# 03_GSM_GPRS_GPS.net
KiCad netlist of a schematic drawn in Altium Designer
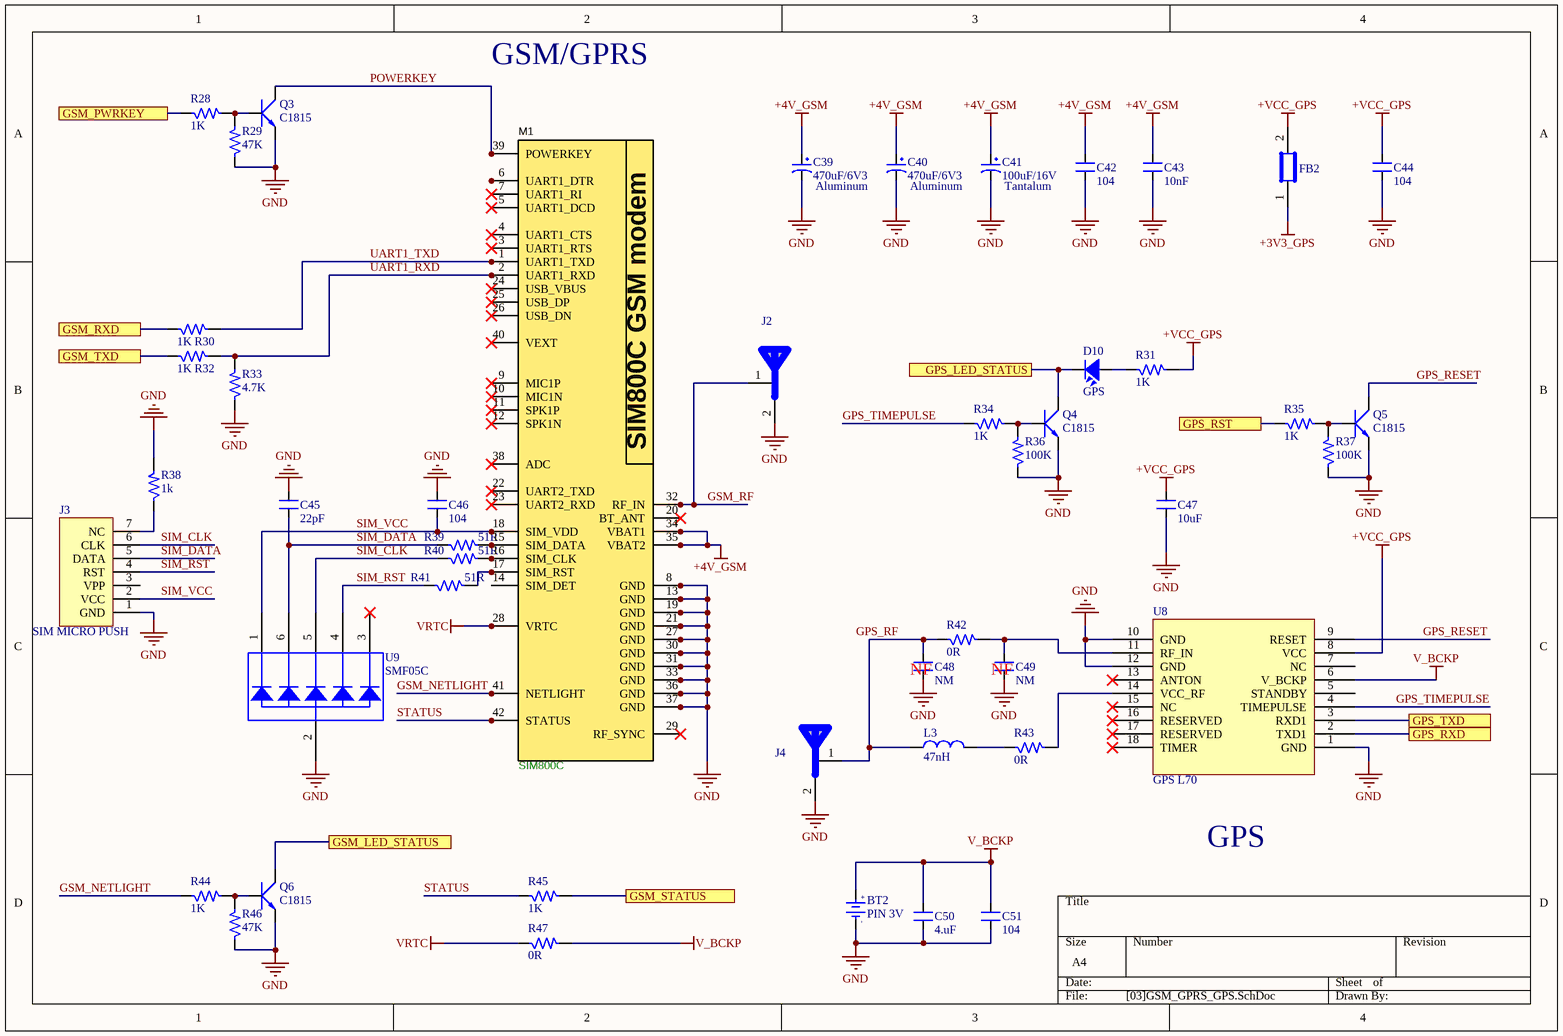
[diagram p0: [03]GSM_GPRS_GPS.SchDoc]

(export (version "E")
  (design (tool "Eeschema 10.0.6"))
  (components
    (comp (ref "BT2")
      (value "PIN 3V")
      (footprint "My Library:CR1220 SMD")
      (description "Battery 3VDC")
      (libsource (lib "GPS_Traking_V1_1") (part "PIN 3V"))
    )
    (comp (ref "C39")
      (value "470uF/6V3")
      (footprint "C_Alu_6.3x7.7")
      (description "Cap Aluminum")
      (libsource (lib "GPS_Traking_V1_1") (part "C-Alu-Tantalum"))
    )
    (comp (ref "C40")
      (value "470uF/6V3")
      (footprint "C_Alu_6.3x7.7")
      (description "Cap Aluminum")
      (libsource (lib "GPS_Traking_V1_1") (part "C-Alu-Tantalum"))
    )
    (comp (ref "C41")
      (value "100uF/16V")
      (footprint "C_7343_40")
      (description "Cap Tantalum 7343")
      (libsource (lib "GPS_Traking_V1_1") (part "C-Alu-Tantalum"))
    )
    (comp (ref "C42")
      (value "104")
      (footprint "CAP_0805")
      (description "Cap SMD")
      (libsource (lib "GPS_Traking_V1_1") (part "CM"))
    )
    (comp (ref "C43")
      (value "10nF")
      (footprint "CAP_0805")
      (description "Cap SMD")
      (libsource (lib "GPS_Traking_V1_1") (part "CM"))
    )
    (comp (ref "C44")
      (value "104")
      (footprint "CAP_0805")
      (description "Cap SMD")
      (libsource (lib "GPS_Traking_V1_1") (part "CM"))
    )
    (comp (ref "C45")
      (value "22pF")
      (footprint "C0603 SMT")
      (description "Cap SMD")
      (libsource (lib "GPS_Traking_V1_1") (part "CM"))
    )
    (comp (ref "C46")
      (value "104")
      (footprint "C0603 SMT")
      (description "Cap SMD")
      (libsource (lib "GPS_Traking_V1_1") (part "CM"))
    )
    (comp (ref "C47")
      (value "10uF")
      (footprint "CAP_0805")
      (description "Cap SMD")
      (libsource (lib "GPS_Traking_V1_1") (part "CM"))
    )
    (comp (ref "C48")
      (value "NM")
      (footprint "C0603 SMT")
      (description "Cap SMD")
      (libsource (lib "GPS_Traking_V1_1") (part "CM"))
    )
    (comp (ref "C49")
      (value "NM")
      (footprint "C0603 SMT")
      (description "Cap SMD")
      (libsource (lib "GPS_Traking_V1_1") (part "CM"))
    )
    (comp (ref "C50")
      (value "4.uF")
      (footprint "SM-1210")
      (description "Cap SMD")
      (libsource (lib "GPS_Traking_V1_1") (part "CM"))
    )
    (comp (ref "C51")
      (value "104")
      (footprint "CAP_0805")
      (description "Cap SMD")
      (libsource (lib "GPS_Traking_V1_1") (part "CM"))
    )
    (comp (ref "D10")
      (value "GPS")
      (footprint "LED-0805-Red")
      (description "LED Single colour Green and Red")
      (libsource (lib "GPS_Traking_V1_1") (part "LED"))
    )
    (comp (ref "FB2")
      (value "BLM21PG600SN1D")
      (footprint "R0805")
      (description "Ferrite Bead")
      (libsource (lib "GPS_Traking_V1_1") (part "Ferrite Bead"))
    )
    (comp (ref "J2")
      (value "GPS_ANTENNA")
      (footprint "Antenna-MCX5.08-H5")
      (libsource (lib "GPS_Traking_V1_1") (part "ANTEN"))
    )
    (comp (ref "J3")
      (value "SIM MICRO PUSH")
      (footprint "My Library:MICROSIM_PUSH")
      (libsource (lib "My Library") (part "SIM MICRO PUSH"))
    )
    (comp (ref "J4")
      (value "GPS_ANTENNA")
      (footprint "Antenna-MCX5.08-H5")
      (libsource (lib "GPS_Traking_V1_1") (part "ANTEN"))
    )
    (comp (ref "L3")
      (value "47nH")
      (footprint "RES-SMD-0805")
      (description "Inductor")
      (libsource (lib "GPS_Traking_V1_1") (part "L1"))
    )
    (comp (ref "M1")
      (value "SIM800C")
      (footprint "SIM800C")
      (libsource (lib "GPS_Traking_V1_1") (part "SIM800C"))
    )
    (comp (ref "Q3")
      (value "C1815")
      (footprint "SOT23B")
      (description "NPN 600mW, ECB")
      (libsource (lib "GPS_Traking_V1_1") (part "C1815"))
    )
    (comp (ref "Q4")
      (value "C1815")
      (footprint "SOT23B")
      (description "NPN 600mW, ECB")
      (libsource (lib "GPS_Traking_V1_1") (part "C1815"))
    )
    (comp (ref "Q5")
      (value "C1815")
      (footprint "SOT23B")
      (description "NPN 600mW, ECB")
      (libsource (lib "GPS_Traking_V1_1") (part "C1815"))
    )
    (comp (ref "Q6")
      (value "C1815")
      (footprint "SOT23B")
      (description "NPN 600mW, ECB")
      (libsource (lib "GPS_Traking_V1_1") (part "C1815"))
    )
    (comp (ref "R28")
      (value "1K")
      (footprint "R0603 -SMT")
      (description "Resistor SMD")
      (libsource (lib "GPS_Traking_V1_1") (part "RM"))
    )
    (comp (ref "R29")
      (value "47K")
      (footprint "R0603 -SMT")
      (description "Resistor SMD")
      (libsource (lib "GPS_Traking_V1_1") (part "RM"))
    )
    (comp (ref "R30")
      (value "1K")
      (footprint "R0603 -SMT")
      (description "Resistor SMD")
      (libsource (lib "GPS_Traking_V1_1") (part "RM"))
    )
    (comp (ref "R31")
      (value "1K")
      (footprint "RES-SMD-0805")
      (description "Resistor SMD")
      (libsource (lib "GPS_Traking_V1_1") (part "RM"))
    )
    (comp (ref "R32")
      (value "1K")
      (footprint "R0603 -SMT")
      (description "Resistor SMD")
      (libsource (lib "GPS_Traking_V1_1") (part "RM"))
    )
    (comp (ref "R33")
      (value "4.7K")
      (footprint "R0603 -SMT")
      (description "Resistor SMD")
      (libsource (lib "GPS_Traking_V1_1") (part "RM"))
    )
    (comp (ref "R34")
      (value "1K")
      (footprint "RES-SMD-0805")
      (description "Resistor SMD")
      (libsource (lib "GPS_Traking_V1_1") (part "RM"))
    )
    (comp (ref "R35")
      (value "1K")
      (footprint "RES-SMD-0805")
      (description "Resistor SMD")
      (libsource (lib "GPS_Traking_V1_1") (part "RM"))
    )
    (comp (ref "R36")
      (value "100K")
      (footprint "RES-SMD-0805")
      (description "Resistor SMD")
      (libsource (lib "GPS_Traking_V1_1") (part "RM"))
    )
    (comp (ref "R37")
      (value "100K")
      (footprint "RES-SMD-0805")
      (description "Resistor SMD")
      (libsource (lib "GPS_Traking_V1_1") (part "RM"))
    )
    (comp (ref "R38")
      (value "1k")
      (footprint "RES-SMD-0805")
      (description "Resistor SMD")
      (libsource (lib "GPS_Traking_V1_1") (part "RM"))
    )
    (comp (ref "R39")
      (value "51R")
      (footprint "R0603 -SMT")
      (description "Resistor SMD")
      (libsource (lib "GPS_Traking_V1_1") (part "RM"))
    )
    (comp (ref "R40")
      (value "51R")
      (footprint "R0603 -SMT")
      (description "Resistor SMD")
      (libsource (lib "GPS_Traking_V1_1") (part "RM"))
    )
    (comp (ref "R41")
      (value "51R")
      (footprint "R0603 -SMT")
      (description "Resistor SMD")
      (libsource (lib "GPS_Traking_V1_1") (part "RM"))
    )
    (comp (ref "R42")
      (value "0R")
      (footprint "R0603 -SMT")
      (description "Resistor SMD")
      (libsource (lib "GPS_Traking_V1_1") (part "RM"))
    )
    (comp (ref "R43")
      (value "0R")
      (footprint "R0603 -SMT")
      (description "Resistor SMD")
      (libsource (lib "GPS_Traking_V1_1") (part "RM"))
    )
    (comp (ref "R44")
      (value "1K")
      (footprint "R0603 -SMT")
      (description "Resistor SMD")
      (libsource (lib "GPS_Traking_V1_1") (part "RM"))
    )
    (comp (ref "R45")
      (value "1K")
      (footprint "R0603 -SMT")
      (description "Resistor SMD")
      (libsource (lib "GPS_Traking_V1_1") (part "RM"))
    )
    (comp (ref "R46")
      (value "47K")
      (footprint "R0603 -SMT")
      (description "Resistor SMD")
      (libsource (lib "GPS_Traking_V1_1") (part "RM"))
    )
    (comp (ref "R47")
      (value "0R")
      (footprint "RES-SMD-0805")
      (description "Resistor SMD")
      (libsource (lib "GPS_Traking_V1_1") (part "RM"))
    )
    (comp (ref "U8")
      (value "GPS L70")
      (footprint "GPS L70")
      (libsource (lib "GPS_Traking_V1_1") (part "GPS L70"))
    )
    (comp (ref "U9")
      (value "SMF05C")
      (footprint "SOT_363_6")
      (description "ESD Protection")
      (libsource (lib "GPS_Traking_V1_1") (part "SMF05C"))
    )
  )
  (nets
    (net (code "1") (name "+3V3_GPS") (class "Default")
      (node (ref "FB2") (pin "1") (pinfunction "1_1") (pintype "passive"))
    )
    (net (code "2") (name "+4V_GSM") (class "Default")
      (node (ref "C39") (pin "1") (pinfunction "1_1") (pintype "passive"))
      (node (ref "C40") (pin "1") (pinfunction "1_1") (pintype "passive"))
      (node (ref "C41") (pin "1") (pinfunction "1_1") (pintype "passive"))
      (node (ref "C42") (pin "1") (pinfunction "1_1") (pintype "passive"))
      (node (ref "C43") (pin "1") (pinfunction "1_1") (pintype "passive"))
      (node (ref "M1") (pin "34") (pinfunction "VBAT1_34") (pintype "passive"))
      (node (ref "M1") (pin "35") (pinfunction "VBAT2_35") (pintype "passive"))
    )
    (net (code "3") (name "+VCC_GPS") (class "Default")
      (node (ref "C44") (pin "2") (pinfunction "2_2") (pintype "passive"))
      (node (ref "C47") (pin "2") (pinfunction "2_2") (pintype "passive"))
      (node (ref "FB2") (pin "2") (pinfunction "2_2") (pintype "passive"))
      (node (ref "R31") (pin "2") (pinfunction "2_2") (pintype "passive"))
      (node (ref "U8") (pin "8") (pinfunction "VCC_8") (pintype "passive"))
    )
    (net (code "4") (name "/GPS_LED_STATUS") (class "Default")
      (node (ref "D10") (pin "2") (pinfunction "2_2") (pintype "passive"))
      (node (ref "Q4") (pin "2") (pinfunction "C_2") (pintype "passive"))
    )
    (net (code "5") (name "/GPS_RESET") (class "Default")
      (node (ref "Q5") (pin "2") (pinfunction "C_2") (pintype "passive"))
      (node (ref "U8") (pin "9") (pinfunction "RESET_9") (pintype "passive"))
    )
    (net (code "7") (name "/GPS_RST") (class "Default")
      (node (ref "R35") (pin "1") (pinfunction "1_1") (pintype "passive"))
    )
    (net (code "8") (name "/GPS_RXD") (class "Default")
      (node (ref "U8") (pin "2") (pinfunction "TXD1_2") (pintype "passive"))
    )
    (net (code "9") (name "/GPS_TIMEPULSE") (class "Default")
      (node (ref "R34") (pin "1") (pinfunction "1_1") (pintype "passive"))
      (node (ref "U8") (pin "4") (pinfunction "TIMEPULSE_4") (pintype "passive"))
    )
    (net (code "10") (name "/GPS_TXD") (class "Default")
      (node (ref "U8") (pin "3") (pinfunction "RXD1_3") (pintype "passive"))
    )
    (net (code "11") (name "/GSM_LED_STATUS") (class "Default")
      (node (ref "Q6") (pin "2") (pinfunction "C_2") (pintype "passive"))
    )
    (net (code "12") (name "/GSM_NETLIGHT") (class "Default")
      (node (ref "M1") (pin "41") (pinfunction "NETLIGHT_41") (pintype "passive"))
      (node (ref "R44") (pin "1") (pinfunction "1_1") (pintype "passive"))
    )
    (net (code "13") (name "/GSM_PWRKEY") (class "Default")
      (node (ref "R28") (pin "1") (pinfunction "1_1") (pintype "passive"))
    )
    (net (code "14") (name "/GSM_RF") (class "Default")
      (node (ref "J2") (pin "1") (pinfunction "GND_1") (pintype "passive"))
      (node (ref "M1") (pin "32") (pinfunction "RF_IN_32") (pintype "passive"))
    )
    (net (code "15") (name "/GSM_RXD") (class "Default")
      (node (ref "R30") (pin "1") (pinfunction "1_1") (pintype "passive"))
    )
    (net (code "16") (name "/GSM_STATUS") (class "Default")
      (node (ref "R45") (pin "2") (pinfunction "2_2") (pintype "passive"))
    )
    (net (code "17") (name "/GSM_TXD") (class "Default")
      (node (ref "R32") (pin "1") (pinfunction "1_1") (pintype "passive"))
    )
    (net (code "18") (name "/POWERKEY") (class "Default")
      (node (ref "M1") (pin "39") (pinfunction "POWERKEY_39") (pintype "passive"))
      (node (ref "Q3") (pin "2") (pinfunction "C_2") (pintype "passive"))
    )
    (net (code "19") (name "/SIM_CLK") (class "Default")
      (node (ref "J3") (pin "6") (pinfunction "CLK_6") (pintype "passive"))
      (node (ref "R40") (pin "1") (pinfunction "1_1") (pintype "passive"))
      (node (ref "U9") (pin "5") (pinfunction "K4_5") (pintype "power_in"))
    )
    (net (code "20") (name "/SIM_DATA") (class "Default")
      (node (ref "C45") (pin "1") (pinfunction "1_1") (pintype "passive"))
      (node (ref "J3") (pin "5") (pinfunction "DATA_5") (pintype "passive"))
      (node (ref "R39") (pin "1") (pinfunction "1_1") (pintype "passive"))
      (node (ref "U9") (pin "6") (pinfunction "K5_6") (pintype "passive"))
    )
    (net (code "21") (name "/SIM_RST") (class "Default")
      (node (ref "J3") (pin "4") (pinfunction "RST_4") (pintype "passive"))
      (node (ref "R41") (pin "1") (pinfunction "1_1") (pintype "passive"))
      (node (ref "U9") (pin "4") (pinfunction "K3_4") (pintype "passive"))
    )
    (net (code "22") (name "/SIM_VCC") (class "Default")
      (node (ref "C46") (pin "1") (pinfunction "1_1") (pintype "passive"))
      (node (ref "J3") (pin "2") (pinfunction "VCC_2") (pintype "passive"))
      (node (ref "M1") (pin "18") (pinfunction "SIM_VDD_18") (pintype "passive"))
      (node (ref "U9") (pin "1") (pinfunction "K1_1") (pintype "passive"))
    )
    (net (code "23") (name "/STATUS") (class "Default")
      (node (ref "M1") (pin "42") (pinfunction "STATUS_42") (pintype "passive"))
      (node (ref "R45") (pin "1") (pinfunction "1_1") (pintype "passive"))
    )
    (net (code "24") (name "/UART1_RXD") (class "Default")
      (node (ref "M1") (pin "2") (pinfunction "UART1_RXD_2") (pintype "passive"))
      (node (ref "R32") (pin "2") (pinfunction "2_2") (pintype "passive"))
      (node (ref "R33") (pin "2") (pinfunction "2_2") (pintype "passive"))
    )
    (net (code "25") (name "/UART1_TXD") (class "Default")
      (node (ref "M1") (pin "1") (pinfunction "UART1_TXD_1") (pintype "passive"))
      (node (ref "R30") (pin "2") (pinfunction "2_2") (pintype "passive"))
    )
    (net (code "26") (name "GND") (class "Default")
      (node (ref "BT2") (pin "2") (pinfunction "GND_2") (pintype "passive"))
      (node (ref "C39") (pin "2") (pinfunction "2_2") (pintype "passive"))
      (node (ref "C40") (pin "2") (pinfunction "2_2") (pintype "passive"))
      (node (ref "C41") (pin "2") (pinfunction "2_2") (pintype "passive"))
      (node (ref "C42") (pin "2") (pinfunction "2_2") (pintype "passive"))
      (node (ref "C43") (pin "2") (pinfunction "2_2") (pintype "passive"))
      (node (ref "C44") (pin "1") (pinfunction "1_1") (pintype "passive"))
      (node (ref "C45") (pin "2") (pinfunction "2_2") (pintype "passive"))
      (node (ref "C46") (pin "2") (pinfunction "2_2") (pintype "passive"))
      (node (ref "C47") (pin "1") (pinfunction "1_1") (pintype "passive"))
      (node (ref "C48") (pin "1") (pinfunction "1_1") (pintype "passive"))
      (node (ref "C49") (pin "1") (pinfunction "1_1") (pintype "passive"))
      (node (ref "C50") (pin "1") (pinfunction "1_1") (pintype "passive"))
      (node (ref "C51") (pin "1") (pinfunction "1_1") (pintype "passive"))
      (node (ref "J2") (pin "2") (pinfunction "GND_2") (pintype "passive"))
      (node (ref "J3") (pin "1") (pinfunction "GND_1") (pintype "passive"))
      (node (ref "J4") (pin "2") (pinfunction "GND_2") (pintype "passive"))
      (node (ref "M1") (pin "13") (pinfunction "GND_13") (pintype "passive"))
      (node (ref "M1") (pin "19") (pinfunction "GND_19") (pintype "passive"))
      (node (ref "M1") (pin "21") (pinfunction "GND_21") (pintype "passive"))
      (node (ref "M1") (pin "27") (pinfunction "GND_27") (pintype "passive"))
      (node (ref "M1") (pin "30") (pinfunction "GND_30") (pintype "passive"))
      (node (ref "M1") (pin "31") (pinfunction "GND_31") (pintype "passive"))
      (node (ref "M1") (pin "33") (pinfunction "GND_33") (pintype "passive"))
      (node (ref "M1") (pin "36") (pinfunction "GND_36") (pintype "passive"))
      (node (ref "M1") (pin "37") (pinfunction "GND_37") (pintype "passive"))
      (node (ref "M1") (pin "8") (pinfunction "GND_8") (pintype "passive"))
      (node (ref "Q3") (pin "1") (pinfunction "E_1") (pintype "passive"))
      (node (ref "Q4") (pin "1") (pinfunction "E_1") (pintype "passive"))
      (node (ref "Q5") (pin "1") (pinfunction "E_1") (pintype "passive"))
      (node (ref "Q6") (pin "1") (pinfunction "E_1") (pintype "passive"))
      (node (ref "R29") (pin "1") (pinfunction "1_1") (pintype "passive"))
      (node (ref "R33") (pin "1") (pinfunction "1_1") (pintype "passive"))
      (node (ref "R36") (pin "1") (pinfunction "1_1") (pintype "passive"))
      (node (ref "R37") (pin "1") (pinfunction "1_1") (pintype "passive"))
      (node (ref "R38") (pin "2") (pinfunction "2_2") (pintype "passive"))
      (node (ref "R46") (pin "1") (pinfunction "1_1") (pintype "passive"))
      (node (ref "U8") (pin "1") (pinfunction "GND_1") (pintype "passive"))
      (node (ref "U8") (pin "10") (pinfunction "GND_10") (pintype "passive"))
      (node (ref "U8") (pin "12") (pinfunction "GND_12") (pintype "passive"))
      (node (ref "U9") (pin "2") (pinfunction "A_2") (pintype "power_in"))
    )
    (net (code "27") (name "Net-(C48-Pad2)") (class "Default")
      (node (ref "C48") (pin "2") (pinfunction "2_2") (pintype "passive"))
      (node (ref "J4") (pin "1") (pinfunction "GND_1") (pintype "passive"))
      (node (ref "L3") (pin "1") (pinfunction "1_1") (pintype "passive"))
      (node (ref "R42") (pin "1") (pinfunction "1_1") (pintype "passive"))
    )
    (net (code "28") (name "Net-(D10-Pad1)") (class "Default")
      (node (ref "D10") (pin "1") (pinfunction "1_1") (pintype "passive"))
      (node (ref "R31") (pin "1") (pinfunction "1_1") (pintype "passive"))
    )
    (net (code "29") (name "Net-(J3-NC)") (class "Default")
      (node (ref "J3") (pin "7") (pinfunction "NC_7") (pintype "passive"))
      (node (ref "R38") (pin "1") (pinfunction "1_1") (pintype "passive"))
    )
    (net (code "30") (name "Net-(L3-Pad2)") (class "Default")
      (node (ref "L3") (pin "2") (pinfunction "2_2") (pintype "passive"))
      (node (ref "R43") (pin "1") (pinfunction "1_1") (pintype "passive"))
    )
    (net (code "31") (name "Net-(M1-SIM_CLK)") (class "Default")
      (node (ref "M1") (pin "16") (pinfunction "SIM_CLK_16") (pintype "passive"))
      (node (ref "R40") (pin "2") (pinfunction "2_2") (pintype "passive"))
    )
    (net (code "32") (name "Net-(M1-SIM_DATA)") (class "Default")
      (node (ref "M1") (pin "15") (pinfunction "SIM_DATA_15") (pintype "passive"))
      (node (ref "R39") (pin "2") (pinfunction "2_2") (pintype "passive"))
    )
    (net (code "33") (name "Net-(M1-SIM_RST)") (class "Default")
      (node (ref "M1") (pin "17") (pinfunction "SIM_RST_17") (pintype "passive"))
      (node (ref "R41") (pin "2") (pinfunction "2_2") (pintype "passive"))
    )
    (net (code "34") (name "Net-(Q3-B)") (class "Default")
      (node (ref "Q3") (pin "3") (pinfunction "B_3") (pintype "passive"))
      (node (ref "R28") (pin "2") (pinfunction "2_2") (pintype "passive"))
      (node (ref "R29") (pin "2") (pinfunction "2_2") (pintype "passive"))
    )
    (net (code "35") (name "Net-(Q4-B)") (class "Default")
      (node (ref "Q4") (pin "3") (pinfunction "B_3") (pintype "passive"))
      (node (ref "R34") (pin "2") (pinfunction "2_2") (pintype "passive"))
      (node (ref "R36") (pin "2") (pinfunction "2_2") (pintype "passive"))
    )
    (net (code "36") (name "Net-(Q5-B)") (class "Default")
      (node (ref "Q5") (pin "3") (pinfunction "B_3") (pintype "passive"))
      (node (ref "R35") (pin "2") (pinfunction "2_2") (pintype "passive"))
      (node (ref "R37") (pin "2") (pinfunction "2_2") (pintype "passive"))
    )
    (net (code "37") (name "Net-(Q6-B)") (class "Default")
      (node (ref "Q6") (pin "3") (pinfunction "B_3") (pintype "passive"))
      (node (ref "R44") (pin "2") (pinfunction "2_2") (pintype "passive"))
      (node (ref "R46") (pin "2") (pinfunction "2_2") (pintype "passive"))
    )
    (net (code "38") (name "Net-(U8-RF_IN)") (class "Default")
      (node (ref "C49") (pin "2") (pinfunction "2_2") (pintype "passive"))
      (node (ref "R42") (pin "2") (pinfunction "2_2") (pintype "passive"))
      (node (ref "U8") (pin "11") (pinfunction "RF_IN_11") (pintype "passive"))
    )
    (net (code "39") (name "Net-(U8-VCC_RF)") (class "Default")
      (node (ref "R43") (pin "2") (pinfunction "2_2") (pintype "passive"))
      (node (ref "U8") (pin "14") (pinfunction "VCC_RF_14") (pintype "passive"))
    )
    (net (code "40") (name "VRTC") (class "Default")
      (node (ref "M1") (pin "28") (pinfunction "VRTC_28") (pintype "passive"))
      (node (ref "R47") (pin "1") (pinfunction "1_1") (pintype "passive"))
    )
    (net (code "41") (name "V_BCKP") (class "Default")
      (node (ref "BT2") (pin "1") (pinfunction "+3V_1") (pintype "passive"))
      (node (ref "C50") (pin "2") (pinfunction "2_2") (pintype "passive"))
      (node (ref "C51") (pin "2") (pinfunction "2_2") (pintype "passive"))
      (node (ref "R47") (pin "2") (pinfunction "2_2") (pintype "passive"))
      (node (ref "U8") (pin "6") (pinfunction "V_BCKP_6") (pintype "passive"))
    )
    (net (code "42") (name "unconnected-(J3-VPP-Pad3)") (class "Default")
      (node (ref "J3") (pin "3") (pinfunction "VPP_3") (pintype "passive"))
    )
    (net (code "43") (name "unconnected-(M1-ADC-Pad38)") (class "Default")
      (node (ref "M1") (pin "38") (pinfunction "ADC_38") (pintype "passive+no_connect"))
    )
    (net (code "44") (name "unconnected-(M1-BT_ANT-Pad20)") (class "Default")
      (node (ref "M1") (pin "20") (pinfunction "BT_ANT_20") (pintype "passive+no_connect"))
    )
    (net (code "45") (name "unconnected-(M1-MIC1N-Pad10)") (class "Default")
      (node (ref "M1") (pin "10") (pinfunction "MIC1N_10") (pintype "passive+no_connect"))
    )
    (net (code "46") (name "unconnected-(M1-MIC1P-Pad9)") (class "Default")
      (node (ref "M1") (pin "9") (pinfunction "MIC1P_9") (pintype "passive+no_connect"))
    )
    (net (code "47") (name "unconnected-(M1-RF_SYNC-Pad29)") (class "Default")
      (node (ref "M1") (pin "29") (pinfunction "RF_SYNC_29") (pintype "passive+no_connect"))
    )
    (net (code "48") (name "unconnected-(M1-SIM_DET-Pad14)") (class "Default")
      (node (ref "M1") (pin "14") (pinfunction "SIM_DET_14") (pintype "passive"))
    )
    (net (code "49") (name "unconnected-(M1-SPK1N-Pad12)") (class "Default")
      (node (ref "M1") (pin "12") (pinfunction "SPK1N_12") (pintype "passive+no_connect"))
    )
    (net (code "50") (name "unconnected-(M1-SPK1P-Pad11)") (class "Default")
      (node (ref "M1") (pin "11") (pinfunction "SPK1P_11") (pintype "passive+no_connect"))
    )
    (net (code "51") (name "unconnected-(M1-UART1_CTS-Pad4)") (class "Default")
      (node (ref "M1") (pin "4") (pinfunction "UART1_CTS_4") (pintype "passive+no_connect"))
    )
    (net (code "52") (name "unconnected-(M1-UART1_DCD-Pad5)") (class "Default")
      (node (ref "M1") (pin "5") (pinfunction "UART1_DCD_5") (pintype "passive+no_connect"))
    )
    (net (code "53") (name "unconnected-(M1-UART1_DTR-Pad6)") (class "Default")
      (node (ref "M1") (pin "6") (pinfunction "UART1_DTR_6") (pintype "passive"))
    )
    (net (code "54") (name "unconnected-(M1-UART1_RI-Pad7)") (class "Default")
      (node (ref "M1") (pin "7") (pinfunction "UART1_RI_7") (pintype "passive+no_connect"))
    )
    (net (code "55") (name "unconnected-(M1-UART1_RTS-Pad3)") (class "Default")
      (node (ref "M1") (pin "3") (pinfunction "UART1_RTS_3") (pintype "passive+no_connect"))
    )
    (net (code "56") (name "unconnected-(M1-UART2_RXD-Pad23)") (class "Default")
      (node (ref "M1") (pin "23") (pinfunction "UART2_RXD_23") (pintype "passive+no_connect"))
    )
    (net (code "57") (name "unconnected-(M1-UART2_TXD-Pad22)") (class "Default")
      (node (ref "M1") (pin "22") (pinfunction "UART2_TXD_22") (pintype "passive+no_connect"))
    )
    (net (code "58") (name "unconnected-(M1-USB_DN-Pad26)") (class "Default")
      (node (ref "M1") (pin "26") (pinfunction "USB_DN_26") (pintype "passive+no_connect"))
    )
    (net (code "59") (name "unconnected-(M1-USB_DP-Pad25)") (class "Default")
      (node (ref "M1") (pin "25") (pinfunction "USB_DP_25") (pintype "passive+no_connect"))
    )
    (net (code "60") (name "unconnected-(M1-USB_VBUS-Pad24)") (class "Default")
      (node (ref "M1") (pin "24") (pinfunction "USB_VBUS_24") (pintype "passive+no_connect"))
    )
    (net (code "61") (name "unconnected-(M1-VEXT-Pad40)") (class "Default")
      (node (ref "M1") (pin "40") (pinfunction "VEXT_40") (pintype "passive+no_connect"))
    )
    (net (code "62") (name "unconnected-(U8-ANTON-Pad13)") (class "Default")
      (node (ref "U8") (pin "13") (pinfunction "ANTON_13") (pintype "passive+no_connect"))
    )
    (net (code "63") (name "unconnected-(U8-NC-Pad7)") (class "Default")
      (node (ref "U8") (pin "7") (pinfunction "NC_7") (pintype "passive"))
    )
    (net (code "64") (name "unconnected-(U8-NC-Pad15)") (class "Default")
      (node (ref "U8") (pin "15") (pinfunction "NC_15") (pintype "passive+no_connect"))
    )
    (net (code "65") (name "unconnected-(U8-RESERVED-Pad16)") (class "Default")
      (node (ref "U8") (pin "16") (pinfunction "RESERVED_16") (pintype "passive+no_connect"))
    )
    (net (code "66") (name "unconnected-(U8-RESERVED-Pad17)") (class "Default")
      (node (ref "U8") (pin "17") (pinfunction "RESERVED_17") (pintype "passive+no_connect"))
    )
    (net (code "67") (name "unconnected-(U8-STANDBY-Pad5)") (class "Default")
      (node (ref "U8") (pin "5") (pinfunction "STANDBY_5") (pintype "passive"))
    )
    (net (code "68") (name "unconnected-(U8-TIMER-Pad18)") (class "Default")
      (node (ref "U8") (pin "18") (pinfunction "TIMER_18") (pintype "passive+no_connect"))
    )
    (net (code "69") (name "unconnected-(U9-K2-Pad3)") (class "Default")
      (node (ref "U9") (pin "3") (pinfunction "K2_3") (pintype "passive+no_connect"))
    )
  )
)
